# ACPowerDistributionConnectors.net
KiCad netlist of a schematic drawn in Altium Designer
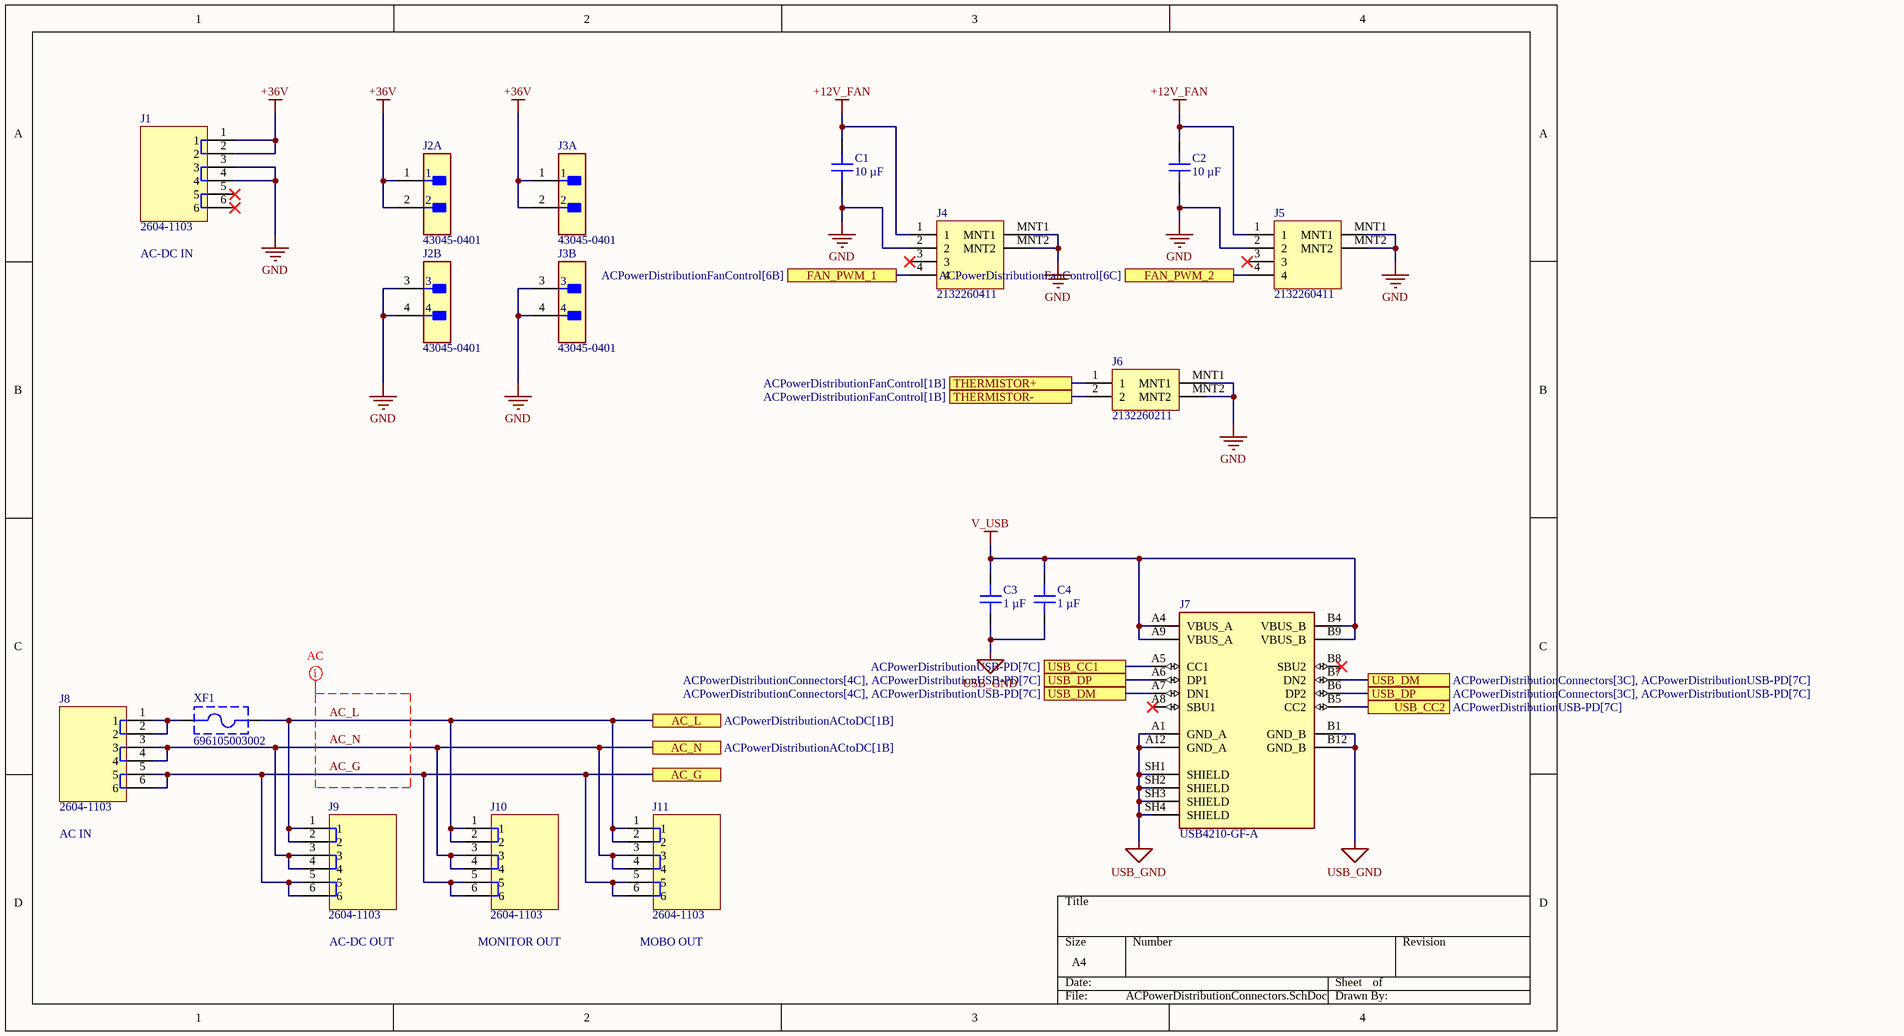
[diagram p0: ACPowerDistributionConnectors.SchDoc]

(export (version "E")
  (design (tool "Eeschema 10.0.6"))
  (components
    (comp (ref "C1")
      (value "10 µF")
      (footprint "CAP 1210_3225 - 1MM")
      (description "CAP CER 10UF 75V X7R 1210")
      (fields
        (field (name "PART NUMBER") "CGA6P1X7R1N106K250AC")
        (field (name "MANUFACTURER") "TDK Corporation")
      )
      (libsource (lib "Celestial Altium Library - altium_library") (part "Capacitor"))
    )
    (comp (ref "C2")
      (value "10 µF")
      (footprint "CAP 1210_3225 - 1MM")
      (description "CAP CER 10UF 75V X7R 1210")
      (fields
        (field (name "PART NUMBER") "CGA6P1X7R1N106K250AC")
        (field (name "MANUFACTURER") "TDK Corporation")
      )
      (libsource (lib "Celestial Altium Library - altium_library") (part "Capacitor"))
    )
    (comp (ref "C3")
      (value "1 µF")
      (footprint "CAP 0603_1608")
      (description "CAP CER 1UF 25V X5R 0603")
      (fields
        (field (name "PART NUMBER") "CL10A105KA8NNNC")
        (field (name "CAPACITANCE") "1 µF")
        (field (name "MANUFACTURER") "Samsung Electro-Mechanics")
      )
      (libsource (lib "Celestial Altium Library - altium_library") (part "Capacitor"))
    )
    (comp (ref "C4")
      (value "1 µF")
      (footprint "CAP 0603_1608")
      (description "CAP CER 1UF 25V X5R 0603")
      (fields
        (field (name "PART NUMBER") "CL10A105KA8NNNC")
        (field (name "CAPACITANCE") "1 µF")
        (field (name "MANUFACTURER") "Samsung Electro-Mechanics")
      )
      (libsource (lib "Celestial Altium Library - altium_library") (part "Capacitor"))
    )
    (comp (ref "J1")
      (value "2604-1103")
      (footprint "2604-1103")
      (libsource (lib "PersonalLibrary") (part "2604-1103"))
    )
    (comp (ref "J2")
      (value "43045-0401")
      (footprint "FP-43045-0401-MFG")
      (description "MICROFIT 3.0 RA HDR W/TH DR 15AU")
      (libsource (lib "Altium Content Vault") (part "fba671f101613090c92597de4a8d9b4"))
    )
    (comp (ref "J3")
      (value "43045-0401")
      (footprint "FP-43045-0401-MFG")
      (description "MICROFIT 3.0 RA HDR W/TH DR 15AU")
      (libsource (lib "Altium Content Vault") (part "fba671f101613090c92597de4a8d9b4"))
    )
    (comp (ref "J4")
      (value "2132260411")
      (footprint "2132260411")
      (libsource (lib "PersonalLibrary") (part "2132260411"))
    )
    (comp (ref "J5")
      (value "2132260411")
      (footprint "2132260411")
      (libsource (lib "PersonalLibrary") (part "2132260411"))
    )
    (comp (ref "J6")
      (value "2132260211")
      (footprint "2132260211")
      (libsource (lib "PersonalLibrary") (part "2132260211"))
    )
    (comp (ref "J7")
      (value "USB4210-GF-A")
      (footprint "USB4210-GF-A")
      (libsource (lib "PersonalLibrary") (part "USB4210-GF-A"))
    )
    (comp (ref "J8")
      (value "2604-1103")
      (footprint "2604-1103")
      (libsource (lib "PersonalLibrary") (part "2604-1103"))
    )
    (comp (ref "J9") (value "2604-1103") (footprint "2604-1103") (libsource (lib "") (part "2604-1103_1")))
    (comp (ref "J10") (value "2604-1103") (footprint "2604-1103") (libsource (lib "") (part "2604-1103_1")))
    (comp (ref "J11") (value "2604-1103") (footprint "2604-1103") (libsource (lib "") (part "2604-1103_1")))
    (comp (ref "XF1")
      (value "696105003002")
      (footprint "696105003002")
      (libsource (lib "Altium Content Vault") (part "Fuse Holder"))
    )
  )
  (nets
    (net (code "1") (name "+12V_FAN") (class "Default")
      (node (ref "C1") (pin "2") (pinfunction "2_2") (pintype "passive"))
      (node (ref "C2") (pin "2") (pinfunction "2_2") (pintype "passive"))
      (node (ref "J4") (pin "1") (pinfunction "1_1") (pintype "passive"))
      (node (ref "J5") (pin "1") (pinfunction "1_1") (pintype "passive"))
    )
    (net (code "2") (name "+36V") (class "Default")
      (node (ref "J1") (pin "1") (pinfunction "1_1") (pintype "passive"))
      (node (ref "J1") (pin "2") (pinfunction "2_2") (pintype "passive"))
      (node (ref "J2") (pin "1") (pinfunction "1_1") (pintype "passive"))
      (node (ref "J2") (pin "2") (pinfunction "2_2") (pintype "passive"))
      (node (ref "J3") (pin "1") (pinfunction "1_1") (pintype "passive"))
      (node (ref "J3") (pin "2") (pinfunction "2_2") (pintype "passive"))
    )
    (net (code "3") (name "/AC_G") (class "Default")
      (node (ref "J10") (pin "5") (pinfunction "5_5") (pintype "passive"))
      (node (ref "J10") (pin "6") (pinfunction "6_6") (pintype "passive"))
      (node (ref "J11") (pin "5") (pinfunction "5_5") (pintype "passive"))
      (node (ref "J11") (pin "6") (pinfunction "6_6") (pintype "passive"))
      (node (ref "J8") (pin "5") (pinfunction "5_5") (pintype "passive"))
      (node (ref "J8") (pin "6") (pinfunction "6_6") (pintype "passive"))
      (node (ref "J9") (pin "5") (pinfunction "5_5") (pintype "passive"))
      (node (ref "J9") (pin "6") (pinfunction "6_6") (pintype "passive"))
    )
    (net (code "4") (name "/AC_L") (class "Default")
      (node (ref "J10") (pin "1") (pinfunction "1_1") (pintype "passive"))
      (node (ref "J10") (pin "2") (pinfunction "2_2") (pintype "passive"))
      (node (ref "J11") (pin "1") (pinfunction "1_1") (pintype "passive"))
      (node (ref "J11") (pin "2") (pinfunction "2_2") (pintype "passive"))
      (node (ref "J9") (pin "1") (pinfunction "1_1") (pintype "passive"))
      (node (ref "J9") (pin "2") (pinfunction "2_2") (pintype "passive"))
      (node (ref "XF1") (pin "2") (pinfunction "2_2") (pintype "passive"))
    )
    (net (code "5") (name "/AC_N") (class "Default")
      (node (ref "J10") (pin "3") (pinfunction "3_3") (pintype "passive"))
      (node (ref "J10") (pin "4") (pinfunction "4_4") (pintype "passive"))
      (node (ref "J11") (pin "3") (pinfunction "3_3") (pintype "passive"))
      (node (ref "J11") (pin "4") (pinfunction "4_4") (pintype "passive"))
      (node (ref "J8") (pin "3") (pinfunction "3_3") (pintype "passive"))
      (node (ref "J8") (pin "4") (pinfunction "4_4") (pintype "passive"))
      (node (ref "J9") (pin "3") (pinfunction "3_3") (pintype "passive"))
      (node (ref "J9") (pin "4") (pinfunction "4_4") (pintype "passive"))
    )
    (net (code "6") (name "/FAN_PWM_1") (class "Default")
      (node (ref "J4") (pin "4") (pinfunction "4_4") (pintype "passive"))
    )
    (net (code "7") (name "/FAN_PWM_2") (class "Default")
      (node (ref "J5") (pin "4") (pinfunction "4_4") (pintype "passive"))
    )
    (net (code "8") (name "/THERMISTOR+") (class "Default")
      (node (ref "J6") (pin "1") (pinfunction "1_1") (pintype "passive"))
    )
    (net (code "9") (name "/THERMISTOR-") (class "Default")
      (node (ref "J6") (pin "2") (pinfunction "2_2") (pintype "passive"))
    )
    (net (code "10") (name "/USB_CC1") (class "Default")
      (node (ref "J7") (pin "A5") (pinfunction "CC1_A5") (pintype "bidirectional"))
    )
    (net (code "11") (name "/USB_CC2") (class "Default")
      (node (ref "J7") (pin "B5") (pinfunction "CC2_B5") (pintype "bidirectional"))
    )
    (net (code "12") (name "/USB_DM") (class "Default")
      (node (ref "J7") (pin "A7") (pinfunction "DN1_A7") (pintype "bidirectional"))
      (node (ref "J7") (pin "B7") (pinfunction "DN2_B7") (pintype "bidirectional"))
    )
    (net (code "13") (name "/USB_DP") (class "Default")
      (node (ref "J7") (pin "A6") (pinfunction "DP1_A6") (pintype "bidirectional"))
      (node (ref "J7") (pin "B6") (pinfunction "DP2_B6") (pintype "bidirectional"))
    )
    (net (code "14") (name "GND") (class "Default")
      (node (ref "C1") (pin "1") (pinfunction "1_1") (pintype "passive"))
      (node (ref "C2") (pin "1") (pinfunction "1_1") (pintype "passive"))
      (node (ref "J1") (pin "3") (pinfunction "3_3") (pintype "passive"))
      (node (ref "J1") (pin "4") (pinfunction "4_4") (pintype "passive"))
      (node (ref "J2") (pin "3") (pinfunction "3_3") (pintype "passive"))
      (node (ref "J2") (pin "4") (pinfunction "4_4") (pintype "passive"))
      (node (ref "J3") (pin "3") (pinfunction "3_3") (pintype "passive"))
      (node (ref "J3") (pin "4") (pinfunction "4_4") (pintype "passive"))
      (node (ref "J4") (pin "2") (pinfunction "2_2") (pintype "passive"))
      (node (ref "J4") (pin "MNT1") (pinfunction "MNT1_MNT1") (pintype "passive"))
      (node (ref "J4") (pin "MNT2") (pinfunction "MNT2_MNT2") (pintype "passive"))
      (node (ref "J5") (pin "2") (pinfunction "2_2") (pintype "passive"))
      (node (ref "J5") (pin "MNT1") (pinfunction "MNT1_MNT1") (pintype "passive"))
      (node (ref "J5") (pin "MNT2") (pinfunction "MNT2_MNT2") (pintype "passive"))
      (node (ref "J6") (pin "MNT1") (pinfunction "MNT1_MNT1") (pintype "passive"))
      (node (ref "J6") (pin "MNT2") (pinfunction "MNT2_MNT2") (pintype "passive"))
    )
    (net (code "15") (name "Net-(J8-Pad1)") (class "Default")
      (node (ref "J8") (pin "1") (pinfunction "1_1") (pintype "passive"))
      (node (ref "J8") (pin "2") (pinfunction "2_2") (pintype "passive"))
      (node (ref "XF1") (pin "1") (pinfunction "1_1") (pintype "passive"))
    )
    (net (code "16") (name "USB_GND") (class "Default")
      (node (ref "C3") (pin "1") (pinfunction "1_1") (pintype "passive"))
      (node (ref "C4") (pin "1") (pinfunction "1_1") (pintype "passive"))
      (node (ref "J7") (pin "A1") (pinfunction "GND_A_A1") (pintype "power_in"))
      (node (ref "J7") (pin "A12") (pinfunction "GND_A_A12") (pintype "power_in"))
      (node (ref "J7") (pin "B1") (pinfunction "GND_B_B1") (pintype "power_in"))
      (node (ref "J7") (pin "B12") (pinfunction "GND_B_B12") (pintype "power_in"))
      (node (ref "J7") (pin "SH1") (pinfunction "SHIELD_SH1") (pintype "passive"))
      (node (ref "J7") (pin "SH2") (pinfunction "SHIELD_SH2") (pintype "passive"))
      (node (ref "J7") (pin "SH3") (pinfunction "SHIELD_SH3") (pintype "passive"))
      (node (ref "J7") (pin "SH4") (pinfunction "SHIELD_SH4") (pintype "passive"))
    )
    (net (code "17") (name "V_USB") (class "Default")
      (node (ref "C3") (pin "2") (pinfunction "2_2") (pintype "passive"))
      (node (ref "C4") (pin "2") (pinfunction "2_2") (pintype "passive"))
      (node (ref "J7") (pin "A4") (pinfunction "VBUS_A_A4") (pintype "power_in"))
      (node (ref "J7") (pin "A9") (pinfunction "VBUS_A_A9") (pintype "power_in"))
      (node (ref "J7") (pin "B4") (pinfunction "VBUS_B_B4") (pintype "power_in"))
      (node (ref "J7") (pin "B9") (pinfunction "VBUS_B_B9") (pintype "power_in"))
    )
    (net (code "18") (name "unconnected-(J1-Pad5)") (class "Default")
      (node (ref "J1") (pin "5") (pinfunction "5_5") (pintype "passive+no_connect"))
    )
    (net (code "19") (name "unconnected-(J1-Pad6)") (class "Default")
      (node (ref "J1") (pin "6") (pinfunction "6_6") (pintype "passive+no_connect"))
    )
    (net (code "20") (name "unconnected-(J4-Pad3)") (class "Default")
      (node (ref "J4") (pin "3") (pinfunction "3_3") (pintype "passive+no_connect"))
    )
    (net (code "21") (name "unconnected-(J5-Pad3)") (class "Default")
      (node (ref "J5") (pin "3") (pinfunction "3_3") (pintype "passive+no_connect"))
    )
    (net (code "22") (name "unconnected-(J7-SBU1-PadA8)") (class "Default")
      (node (ref "J7") (pin "A8") (pinfunction "SBU1_A8") (pintype "bidirectional+no_connect"))
    )
    (net (code "23") (name "unconnected-(J7-SBU2-PadB8)") (class "Default")
      (node (ref "J7") (pin "B8") (pinfunction "SBU2_B8") (pintype "bidirectional+no_connect"))
    )
  )
)
